# nlp_base_0_1.net
KiCad netlist of a schematic drawn in EasyEDA
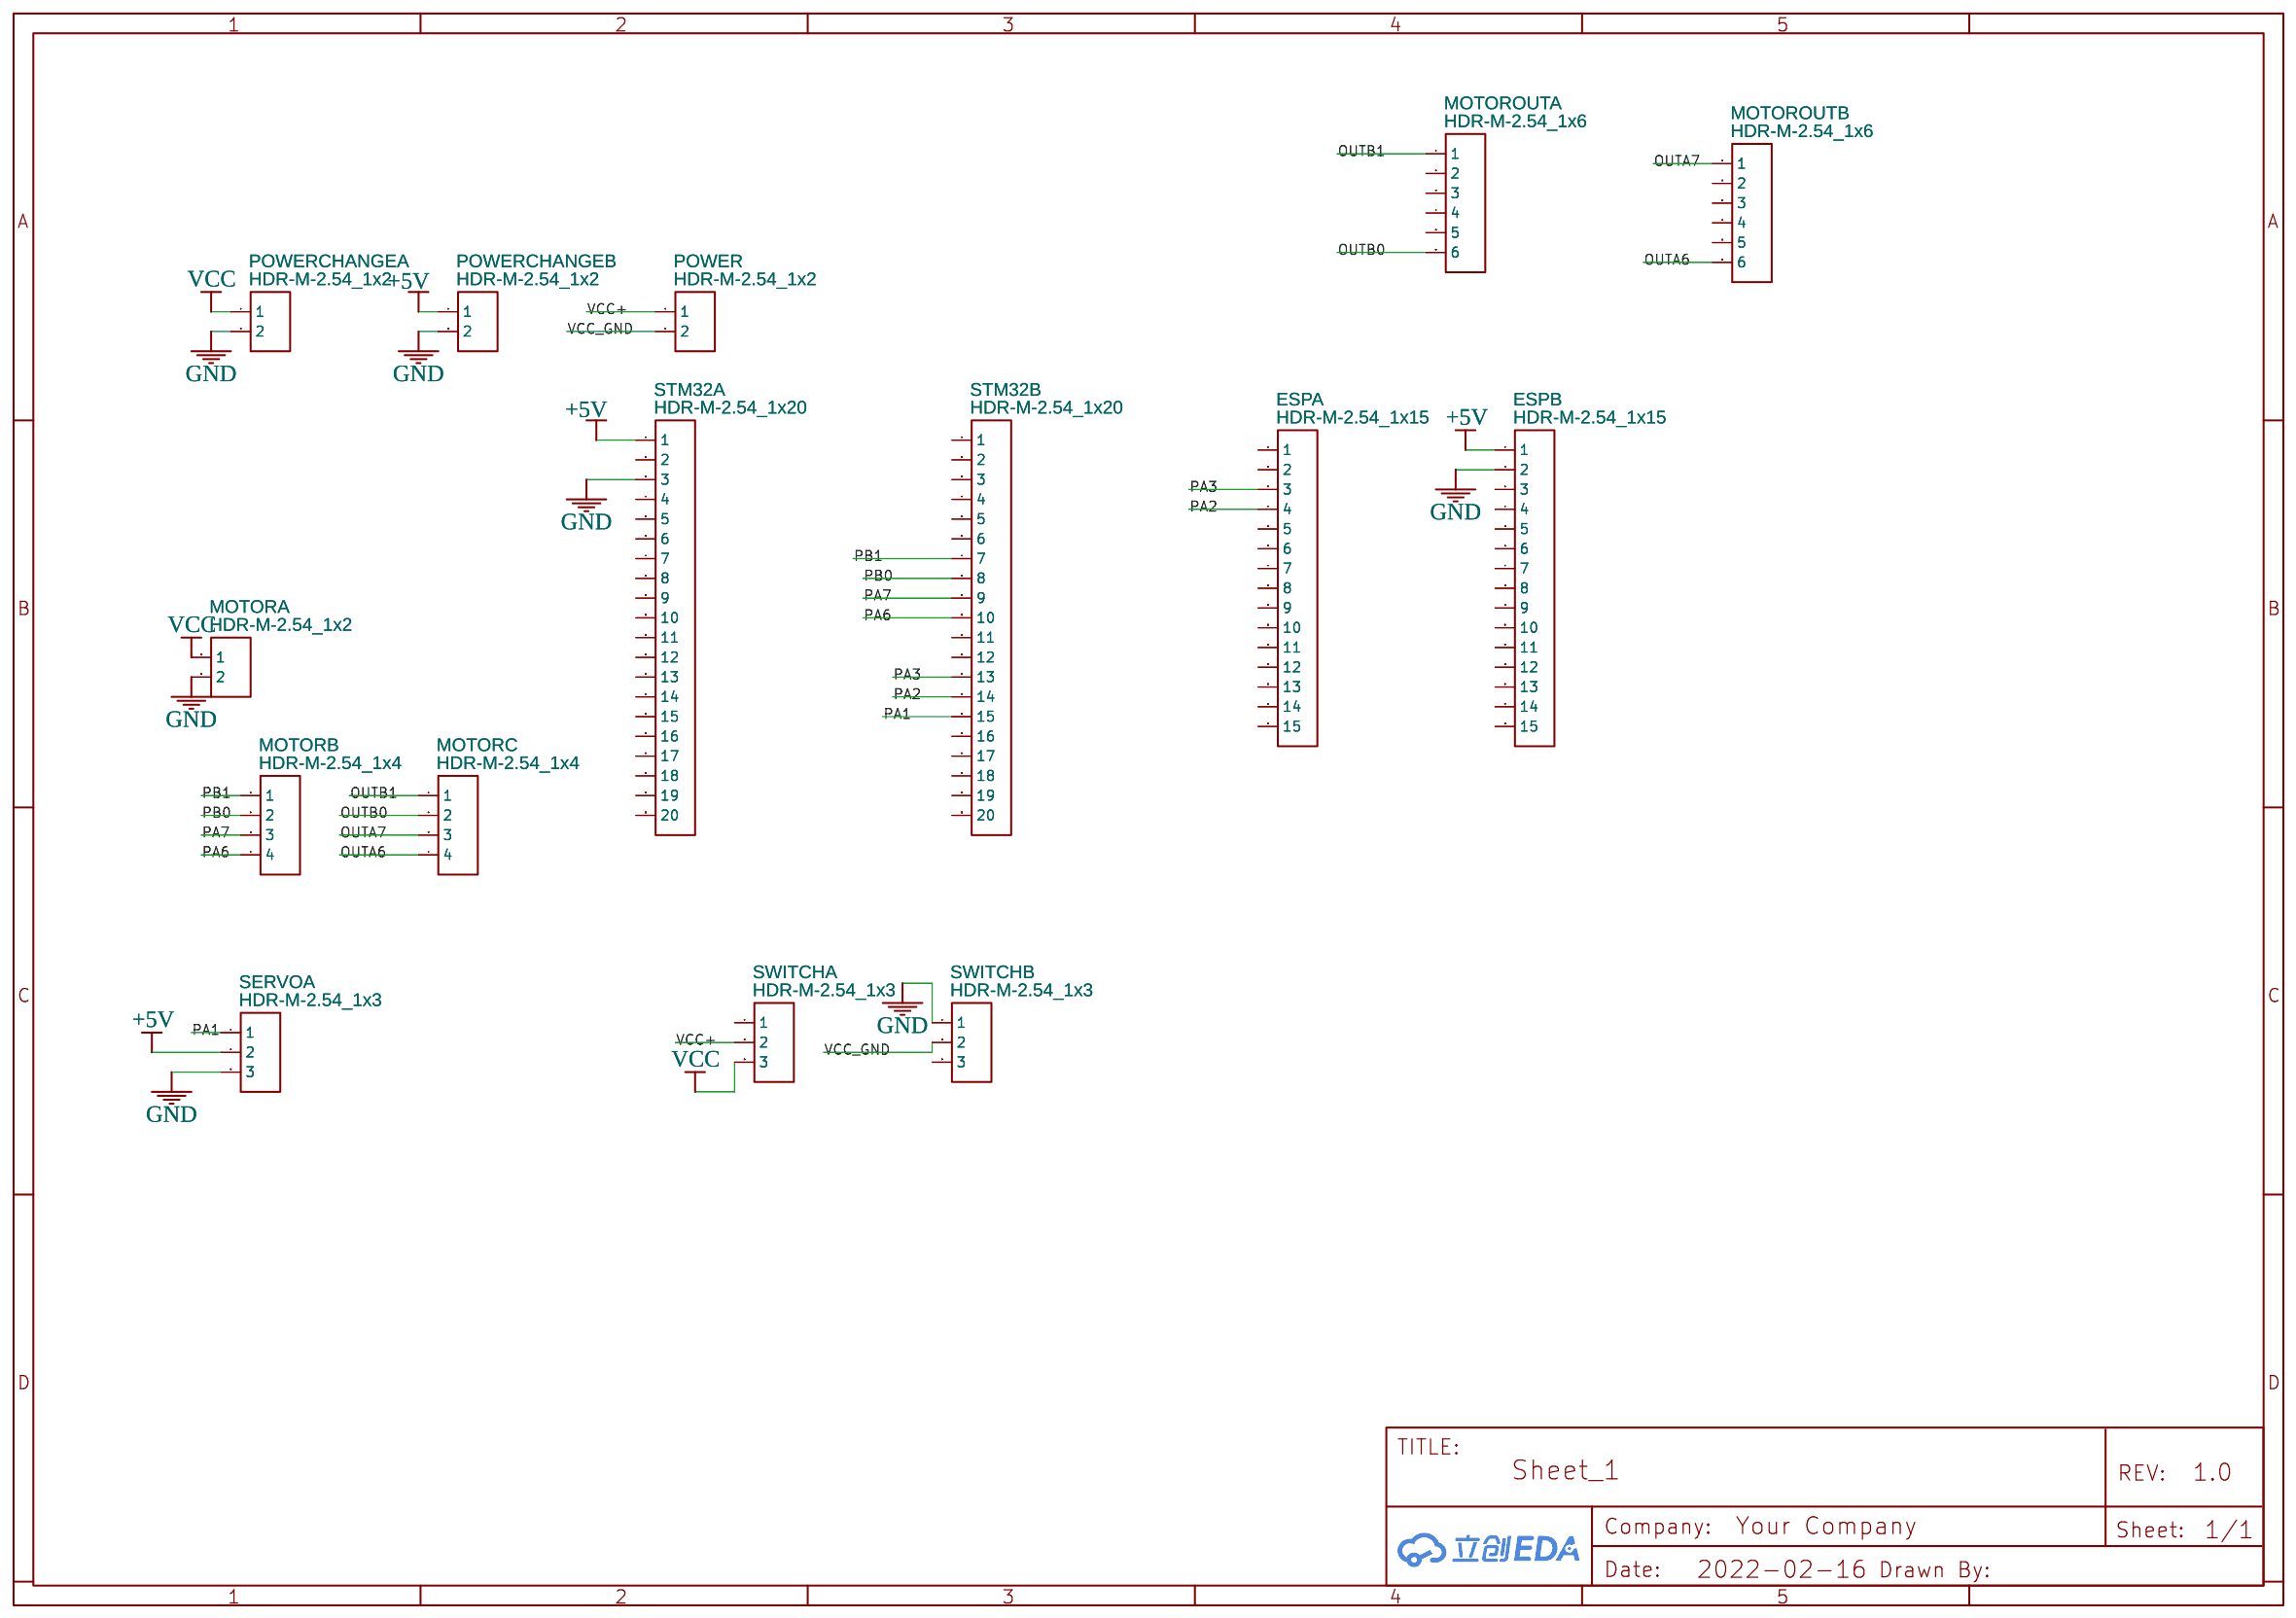
[diagram p0: schematic sheet]

(export (version "E")
  (design (tool "Eeschema 10.0.6"))
  (components
    (comp (ref "ESPA")
      (value "HDR-M-2.54_1x15")
      (fields (field (name "BOM_Supplier Part") "C124373"))
      (libsource (lib "") (part "HDR-M-2.54_1x15"))
    )
    (comp (ref "ESPB")
      (value "HDR-M-2.54_1x15")
      (fields (field (name "BOM_Supplier Part") "C124373"))
      (libsource (lib "") (part "HDR-M-2.54_1x15_1"))
    )
    (comp (ref "MOTORA")
      (value "HDR-M-2.54_1x2")
      (fields (field (name "BOM_Supplier Part") "C124375"))
      (libsource (lib "") (part "HDR-M-2.54_1x2"))
    )
    (comp (ref "MOTORB")
      (value "HDR-M-2.54_1x4")
      (fields (field (name "BOM_Supplier Part") "C124378"))
      (libsource (lib "") (part "HDR-M-2.54_1x4"))
    )
    (comp (ref "MOTORC")
      (value "HDR-M-2.54_1x4")
      (fields (field (name "BOM_Supplier Part") "C124378"))
      (libsource (lib "") (part "HDR-M-2.54_1x4_1"))
    )
    (comp (ref "MOTOROUTA")
      (value "HDR-M-2.54_1x6")
      (fields (field (name "BOM_Supplier Part") "C190819"))
      (libsource (lib "") (part "HDR-M-2.54_1x6"))
    )
    (comp (ref "MOTOROUTB")
      (value "HDR-M-2.54_1x6")
      (fields (field (name "BOM_Supplier Part") "C190819"))
      (libsource (lib "") (part "HDR-M-2.54_1x6_1"))
    )
    (comp (ref "POWER")
      (value "HDR-M-2.54_1x2")
      (fields (field (name "BOM_Supplier Part") "C124375"))
      (libsource (lib "") (part "HDR-M-2.54_1x2_2"))
    )
    (comp (ref "POWERCHANGEA")
      (value "HDR-M-2.54_1x2")
      (fields (field (name "BOM_Supplier Part") "C124375"))
      (libsource (lib "") (part "HDR-M-2.54_1x2_1"))
    )
    (comp (ref "POWERCHANGEB")
      (value "HDR-M-2.54_1x2")
      (fields (field (name "BOM_Supplier Part") "C124375"))
      (libsource (lib "") (part "HDR-M-2.54_1x2_3"))
    )
    (comp (ref "SERVOA")
      (value "HDR-M-2.54_1x3")
      (fields (field (name "BOM_Supplier Part") "C180248"))
      (libsource (lib "") (part "HDR-M-2.54_1x3"))
    )
    (comp (ref "STM32A")
      (value "HDR-M-2.54_1x20")
      (fields (field (name "BOM_Supplier Part") "C50981"))
      (libsource (lib "") (part "HDR-M-2.54_1x20_1"))
    )
    (comp (ref "STM32B")
      (value "HDR-M-2.54_1x20")
      (fields (field (name "BOM_Supplier Part") "C50981"))
      (libsource (lib "") (part "HDR-M-2.54_1x20"))
    )
    (comp (ref "SWITCHA")
      (value "HDR-M-2.54_1x3")
      (fields (field (name "BOM_Supplier Part") "C180248"))
      (libsource (lib "") (part "HDR-M-2.54_1x3_1"))
    )
    (comp (ref "SWITCHB")
      (value "HDR-M-2.54_1x3")
      (fields (field (name "BOM_Supplier Part") "C180248"))
      (libsource (lib "") (part "HDR-M-2.54_1x3_2"))
    )
  )
  (nets
    (net (code "1") (name "+5V") (class "Default")
      (node (ref "ESPB") (pin "1") (pinfunction "1_1") (pintype "unspecified"))
      (node (ref "POWERCHANGEB") (pin "1") (pinfunction "1_1") (pintype "unspecified"))
      (node (ref "SERVOA") (pin "2") (pinfunction "2_2") (pintype "input"))
      (node (ref "STM32A") (pin "1") (pinfunction "1_1") (pintype "unspecified"))
    )
    (net (code "2") (name "/OUTA6") (class "Default")
      (node (ref "MOTORC") (pin "4") (pinfunction "4_4") (pintype "unspecified"))
      (node (ref "MOTOROUTB") (pin "6") (pinfunction "6_6") (pintype "input"))
    )
    (net (code "3") (name "/OUTA7") (class "Default")
      (node (ref "MOTORC") (pin "3") (pinfunction "3_3") (pintype "unspecified"))
      (node (ref "MOTOROUTB") (pin "1") (pinfunction "1_1") (pintype "input"))
    )
    (net (code "4") (name "/OUTB0") (class "Default")
      (node (ref "MOTORC") (pin "2") (pinfunction "2_2") (pintype "unspecified"))
      (node (ref "MOTOROUTA") (pin "6") (pinfunction "6_6") (pintype "input"))
    )
    (net (code "5") (name "/OUTB1") (class "Default")
      (node (ref "MOTORC") (pin "1") (pinfunction "1_1") (pintype "unspecified"))
      (node (ref "MOTOROUTA") (pin "1") (pinfunction "1_1") (pintype "input"))
    )
    (net (code "6") (name "/PA1") (class "Default")
      (node (ref "SERVOA") (pin "1") (pinfunction "1_1") (pintype "input"))
      (node (ref "STM32B") (pin "15") (pinfunction "15_15") (pintype "unspecified"))
    )
    (net (code "7") (name "/PA2") (class "Default")
      (node (ref "ESPA") (pin "4") (pinfunction "4_4") (pintype "unspecified"))
      (node (ref "STM32B") (pin "14") (pinfunction "14_14") (pintype "unspecified"))
    )
    (net (code "8") (name "/PA3") (class "Default")
      (node (ref "ESPA") (pin "3") (pinfunction "3_3") (pintype "unspecified"))
      (node (ref "STM32B") (pin "13") (pinfunction "13_13") (pintype "unspecified"))
    )
    (net (code "9") (name "/PA6") (class "Default")
      (node (ref "MOTORB") (pin "4") (pinfunction "4_4") (pintype "unspecified"))
      (node (ref "STM32B") (pin "10") (pinfunction "10_10") (pintype "unspecified"))
    )
    (net (code "10") (name "/PA7") (class "Default")
      (node (ref "MOTORB") (pin "3") (pinfunction "3_3") (pintype "unspecified"))
      (node (ref "STM32B") (pin "9") (pinfunction "9_9") (pintype "unspecified"))
    )
    (net (code "11") (name "/PB0") (class "Default")
      (node (ref "MOTORB") (pin "2") (pinfunction "2_2") (pintype "unspecified"))
      (node (ref "STM32B") (pin "8") (pinfunction "8_8") (pintype "unspecified"))
    )
    (net (code "12") (name "/PB1") (class "Default")
      (node (ref "MOTORB") (pin "1") (pinfunction "1_1") (pintype "unspecified"))
      (node (ref "STM32B") (pin "7") (pinfunction "7_7") (pintype "unspecified"))
    )
    (net (code "13") (name "/VCC+") (class "Default")
      (node (ref "POWER") (pin "1") (pinfunction "1_1") (pintype "unspecified"))
      (node (ref "SWITCHA") (pin "2") (pinfunction "2_2") (pintype "input"))
    )
    (net (code "14") (name "/VCC_GND") (class "Default")
      (node (ref "POWER") (pin "2") (pinfunction "2_2") (pintype "unspecified"))
      (node (ref "SWITCHB") (pin "2") (pinfunction "2_2") (pintype "input"))
    )
    (net (code "15") (name "GND") (class "Default")
      (node (ref "ESPB") (pin "2") (pinfunction "2_2") (pintype "unspecified"))
      (node (ref "MOTORA") (pin "2") (pinfunction "2_2") (pintype "unspecified"))
      (node (ref "POWERCHANGEA") (pin "2") (pinfunction "2_2") (pintype "unspecified"))
      (node (ref "POWERCHANGEB") (pin "2") (pinfunction "2_2") (pintype "unspecified"))
      (node (ref "SERVOA") (pin "3") (pinfunction "3_3") (pintype "input"))
      (node (ref "STM32A") (pin "3") (pinfunction "3_3") (pintype "unspecified"))
      (node (ref "SWITCHB") (pin "1") (pinfunction "1_1") (pintype "input"))
    )
    (net (code "16") (name "VCC") (class "Default")
      (node (ref "MOTORA") (pin "1") (pinfunction "1_1") (pintype "unspecified"))
      (node (ref "POWERCHANGEA") (pin "1") (pinfunction "1_1") (pintype "unspecified"))
      (node (ref "SWITCHA") (pin "3") (pinfunction "3_3") (pintype "input"))
    )
    (net (code "17") (name "unconnected-(ESPA-Pad1)") (class "Default")
      (node (ref "ESPA") (pin "1") (pinfunction "1_1") (pintype "unspecified"))
    )
    (net (code "18") (name "unconnected-(ESPA-Pad2)") (class "Default")
      (node (ref "ESPA") (pin "2") (pinfunction "2_2") (pintype "unspecified"))
    )
    (net (code "19") (name "unconnected-(ESPA-Pad5)") (class "Default")
      (node (ref "ESPA") (pin "5") (pinfunction "5_5") (pintype "unspecified"))
    )
    (net (code "20") (name "unconnected-(ESPA-Pad6)") (class "Default")
      (node (ref "ESPA") (pin "6") (pinfunction "6_6") (pintype "unspecified"))
    )
    (net (code "21") (name "unconnected-(ESPA-Pad7)") (class "Default")
      (node (ref "ESPA") (pin "7") (pinfunction "7_7") (pintype "unspecified"))
    )
    (net (code "22") (name "unconnected-(ESPA-Pad8)") (class "Default")
      (node (ref "ESPA") (pin "8") (pinfunction "8_8") (pintype "unspecified"))
    )
    (net (code "23") (name "unconnected-(ESPA-Pad9)") (class "Default")
      (node (ref "ESPA") (pin "9") (pinfunction "9_9") (pintype "unspecified"))
    )
    (net (code "24") (name "unconnected-(ESPA-Pad10)") (class "Default")
      (node (ref "ESPA") (pin "10") (pinfunction "10_10") (pintype "unspecified"))
    )
    (net (code "25") (name "unconnected-(ESPA-Pad11)") (class "Default")
      (node (ref "ESPA") (pin "11") (pinfunction "11_11") (pintype "unspecified"))
    )
    (net (code "26") (name "unconnected-(ESPA-Pad12)") (class "Default")
      (node (ref "ESPA") (pin "12") (pinfunction "12_12") (pintype "unspecified"))
    )
    (net (code "27") (name "unconnected-(ESPA-Pad13)") (class "Default")
      (node (ref "ESPA") (pin "13") (pinfunction "13_13") (pintype "unspecified"))
    )
    (net (code "28") (name "unconnected-(ESPA-Pad14)") (class "Default")
      (node (ref "ESPA") (pin "14") (pinfunction "14_14") (pintype "unspecified"))
    )
    (net (code "29") (name "unconnected-(ESPA-Pad15)") (class "Default")
      (node (ref "ESPA") (pin "15") (pinfunction "15_15") (pintype "unspecified"))
    )
    (net (code "30") (name "unconnected-(ESPB-Pad3)") (class "Default")
      (node (ref "ESPB") (pin "3") (pinfunction "3_3") (pintype "unspecified"))
    )
    (net (code "31") (name "unconnected-(ESPB-Pad4)") (class "Default")
      (node (ref "ESPB") (pin "4") (pinfunction "4_4") (pintype "unspecified"))
    )
    (net (code "32") (name "unconnected-(ESPB-Pad5)") (class "Default")
      (node (ref "ESPB") (pin "5") (pinfunction "5_5") (pintype "unspecified"))
    )
    (net (code "33") (name "unconnected-(ESPB-Pad6)") (class "Default")
      (node (ref "ESPB") (pin "6") (pinfunction "6_6") (pintype "unspecified"))
    )
    (net (code "34") (name "unconnected-(ESPB-Pad7)") (class "Default")
      (node (ref "ESPB") (pin "7") (pinfunction "7_7") (pintype "unspecified"))
    )
    (net (code "35") (name "unconnected-(ESPB-Pad8)") (class "Default")
      (node (ref "ESPB") (pin "8") (pinfunction "8_8") (pintype "unspecified"))
    )
    (net (code "36") (name "unconnected-(ESPB-Pad9)") (class "Default")
      (node (ref "ESPB") (pin "9") (pinfunction "9_9") (pintype "unspecified"))
    )
    (net (code "37") (name "unconnected-(ESPB-Pad10)") (class "Default")
      (node (ref "ESPB") (pin "10") (pinfunction "10_10") (pintype "unspecified"))
    )
    (net (code "38") (name "unconnected-(ESPB-Pad11)") (class "Default")
      (node (ref "ESPB") (pin "11") (pinfunction "11_11") (pintype "unspecified"))
    )
    (net (code "39") (name "unconnected-(ESPB-Pad12)") (class "Default")
      (node (ref "ESPB") (pin "12") (pinfunction "12_12") (pintype "unspecified"))
    )
    (net (code "40") (name "unconnected-(ESPB-Pad13)") (class "Default")
      (node (ref "ESPB") (pin "13") (pinfunction "13_13") (pintype "unspecified"))
    )
    (net (code "41") (name "unconnected-(ESPB-Pad14)") (class "Default")
      (node (ref "ESPB") (pin "14") (pinfunction "14_14") (pintype "unspecified"))
    )
    (net (code "42") (name "unconnected-(ESPB-Pad15)") (class "Default")
      (node (ref "ESPB") (pin "15") (pinfunction "15_15") (pintype "unspecified"))
    )
    (net (code "43") (name "unconnected-(MOTOROUTA-Pad2)") (class "Default")
      (node (ref "MOTOROUTA") (pin "2") (pinfunction "2_2") (pintype "input"))
    )
    (net (code "44") (name "unconnected-(MOTOROUTA-Pad3)") (class "Default")
      (node (ref "MOTOROUTA") (pin "3") (pinfunction "3_3") (pintype "input"))
    )
    (net (code "45") (name "unconnected-(MOTOROUTA-Pad4)") (class "Default")
      (node (ref "MOTOROUTA") (pin "4") (pinfunction "4_4") (pintype "input"))
    )
    (net (code "46") (name "unconnected-(MOTOROUTA-Pad5)") (class "Default")
      (node (ref "MOTOROUTA") (pin "5") (pinfunction "5_5") (pintype "input"))
    )
    (net (code "47") (name "unconnected-(MOTOROUTB-Pad2)") (class "Default")
      (node (ref "MOTOROUTB") (pin "2") (pinfunction "2_2") (pintype "input"))
    )
    (net (code "48") (name "unconnected-(MOTOROUTB-Pad3)") (class "Default")
      (node (ref "MOTOROUTB") (pin "3") (pinfunction "3_3") (pintype "input"))
    )
    (net (code "49") (name "unconnected-(MOTOROUTB-Pad4)") (class "Default")
      (node (ref "MOTOROUTB") (pin "4") (pinfunction "4_4") (pintype "input"))
    )
    (net (code "50") (name "unconnected-(MOTOROUTB-Pad5)") (class "Default")
      (node (ref "MOTOROUTB") (pin "5") (pinfunction "5_5") (pintype "input"))
    )
    (net (code "51") (name "unconnected-(STM32A-Pad2)") (class "Default")
      (node (ref "STM32A") (pin "2") (pinfunction "2_2") (pintype "unspecified"))
    )
    (net (code "52") (name "unconnected-(STM32A-Pad4)") (class "Default")
      (node (ref "STM32A") (pin "4") (pinfunction "4_4") (pintype "unspecified"))
    )
    (net (code "53") (name "unconnected-(STM32A-Pad5)") (class "Default")
      (node (ref "STM32A") (pin "5") (pinfunction "5_5") (pintype "unspecified"))
    )
    (net (code "54") (name "unconnected-(STM32A-Pad6)") (class "Default")
      (node (ref "STM32A") (pin "6") (pinfunction "6_6") (pintype "unspecified"))
    )
    (net (code "55") (name "unconnected-(STM32A-Pad7)") (class "Default")
      (node (ref "STM32A") (pin "7") (pinfunction "7_7") (pintype "unspecified"))
    )
    (net (code "56") (name "unconnected-(STM32A-Pad8)") (class "Default")
      (node (ref "STM32A") (pin "8") (pinfunction "8_8") (pintype "unspecified"))
    )
    (net (code "57") (name "unconnected-(STM32A-Pad9)") (class "Default")
      (node (ref "STM32A") (pin "9") (pinfunction "9_9") (pintype "unspecified"))
    )
    (net (code "58") (name "unconnected-(STM32A-Pad10)") (class "Default")
      (node (ref "STM32A") (pin "10") (pinfunction "10_10") (pintype "unspecified"))
    )
    (net (code "59") (name "unconnected-(STM32A-Pad11)") (class "Default")
      (node (ref "STM32A") (pin "11") (pinfunction "11_11") (pintype "unspecified"))
    )
    (net (code "60") (name "unconnected-(STM32A-Pad12)") (class "Default")
      (node (ref "STM32A") (pin "12") (pinfunction "12_12") (pintype "unspecified"))
    )
    (net (code "61") (name "unconnected-(STM32A-Pad13)") (class "Default")
      (node (ref "STM32A") (pin "13") (pinfunction "13_13") (pintype "unspecified"))
    )
    (net (code "62") (name "unconnected-(STM32A-Pad14)") (class "Default")
      (node (ref "STM32A") (pin "14") (pinfunction "14_14") (pintype "unspecified"))
    )
    (net (code "63") (name "unconnected-(STM32A-Pad15)") (class "Default")
      (node (ref "STM32A") (pin "15") (pinfunction "15_15") (pintype "unspecified"))
    )
    (net (code "64") (name "unconnected-(STM32A-Pad16)") (class "Default")
      (node (ref "STM32A") (pin "16") (pinfunction "16_16") (pintype "unspecified"))
    )
    (net (code "65") (name "unconnected-(STM32A-Pad17)") (class "Default")
      (node (ref "STM32A") (pin "17") (pinfunction "17_17") (pintype "unspecified"))
    )
    (net (code "66") (name "unconnected-(STM32A-Pad18)") (class "Default")
      (node (ref "STM32A") (pin "18") (pinfunction "18_18") (pintype "unspecified"))
    )
    (net (code "67") (name "unconnected-(STM32A-Pad19)") (class "Default")
      (node (ref "STM32A") (pin "19") (pinfunction "19_19") (pintype "unspecified"))
    )
    (net (code "68") (name "unconnected-(STM32A-Pad20)") (class "Default")
      (node (ref "STM32A") (pin "20") (pinfunction "20_20") (pintype "unspecified"))
    )
    (net (code "69") (name "unconnected-(STM32B-Pad1)") (class "Default")
      (node (ref "STM32B") (pin "1") (pinfunction "1_1") (pintype "unspecified"))
    )
    (net (code "70") (name "unconnected-(STM32B-Pad2)") (class "Default")
      (node (ref "STM32B") (pin "2") (pinfunction "2_2") (pintype "unspecified"))
    )
    (net (code "71") (name "unconnected-(STM32B-Pad3)") (class "Default")
      (node (ref "STM32B") (pin "3") (pinfunction "3_3") (pintype "unspecified"))
    )
    (net (code "72") (name "unconnected-(STM32B-Pad4)") (class "Default")
      (node (ref "STM32B") (pin "4") (pinfunction "4_4") (pintype "unspecified"))
    )
    (net (code "73") (name "unconnected-(STM32B-Pad5)") (class "Default")
      (node (ref "STM32B") (pin "5") (pinfunction "5_5") (pintype "unspecified"))
    )
    (net (code "74") (name "unconnected-(STM32B-Pad6)") (class "Default")
      (node (ref "STM32B") (pin "6") (pinfunction "6_6") (pintype "unspecified"))
    )
    (net (code "75") (name "unconnected-(STM32B-Pad11)") (class "Default")
      (node (ref "STM32B") (pin "11") (pinfunction "11_11") (pintype "unspecified"))
    )
    (net (code "76") (name "unconnected-(STM32B-Pad12)") (class "Default")
      (node (ref "STM32B") (pin "12") (pinfunction "12_12") (pintype "unspecified"))
    )
    (net (code "77") (name "unconnected-(STM32B-Pad16)") (class "Default")
      (node (ref "STM32B") (pin "16") (pinfunction "16_16") (pintype "unspecified"))
    )
    (net (code "78") (name "unconnected-(STM32B-Pad17)") (class "Default")
      (node (ref "STM32B") (pin "17") (pinfunction "17_17") (pintype "unspecified"))
    )
    (net (code "79") (name "unconnected-(STM32B-Pad18)") (class "Default")
      (node (ref "STM32B") (pin "18") (pinfunction "18_18") (pintype "unspecified"))
    )
    (net (code "80") (name "unconnected-(STM32B-Pad19)") (class "Default")
      (node (ref "STM32B") (pin "19") (pinfunction "19_19") (pintype "unspecified"))
    )
    (net (code "81") (name "unconnected-(STM32B-Pad20)") (class "Default")
      (node (ref "STM32B") (pin "20") (pinfunction "20_20") (pintype "unspecified"))
    )
    (net (code "82") (name "unconnected-(SWITCHA-Pad1)") (class "Default")
      (node (ref "SWITCHA") (pin "1") (pinfunction "1_1") (pintype "input"))
    )
    (net (code "83") (name "unconnected-(SWITCHB-Pad3)") (class "Default")
      (node (ref "SWITCHB") (pin "3") (pinfunction "3_3") (pintype "input"))
    )
  )
)
